# Power_P2V5.net
KiCad netlist of a schematic drawn in Altium Designer
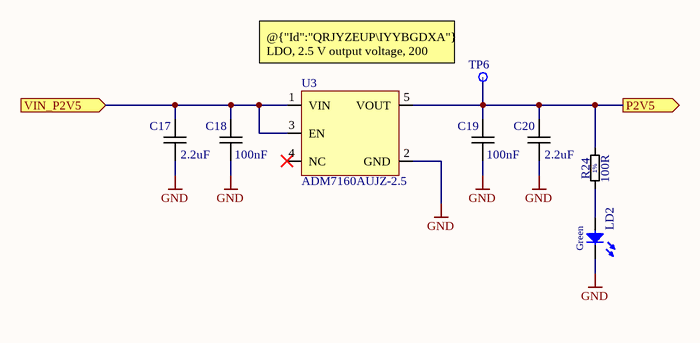
[diagram p0: Power_P2V5.SchDoc]

(export (version "E")
  (design (tool "Eeschema 10.0.6"))
  (components
    (comp (ref "C17")
      (value "2.2uF")
      (footprint "CAPC0603X90N")
      (description "Non-polarised capacitor")
      (fields (field (name "MANUFACTURER PART NUMBER") "GRM188Z71C225KE43D"))
      (libsource (lib "Capacitors") (part "Capacitor - non polarized"))
    )
    (comp (ref "C18")
      (value "100nF")
      (footprint "CAPC0603X90N")
      (description "Non-polarised capacitor")
      (fields (field (name "MANUFACTURER PART NUMBER") "VJ0603Y104KXJCW1BC"))
      (libsource (lib "Capacitors") (part "Capacitor - non polarized"))
    )
    (comp (ref "C19")
      (value "100nF")
      (footprint "CAPC0603X90N")
      (description "Non-polarised capacitor")
      (fields (field (name "MANUFACTURER PART NUMBER") "VJ0603Y104KXJCW1BC"))
      (libsource (lib "Capacitors") (part "Capacitor - non polarized"))
    )
    (comp (ref "C20")
      (value "2.2uF")
      (footprint "CAPC0603X90N")
      (description "Non-polarised capacitor")
      (fields (field (name "MANUFACTURER PART NUMBER") "GRM188Z71C225KE43D"))
      (libsource (lib "Capacitors") (part "Capacitor - non polarized"))
    )
    (comp (ref "LD2")
      (value "Green")
      (footprint "LED_0603X60N")
      (description "SMD mono-color Chip LED, Green, 0603")
      (fields (field (name "MANUFACTURER PART NUMBER") "HSME-C191"))
      (libsource (lib "ICs_and_Semiconductors") (part "LED 1C 2A"))
    )
    (comp (ref "R24")
      (value "100R")
      (footprint "RESC0603X60N")
      (description "General Purpose Thick Film Chip Resistor")
      (fields (field (name "MANUFACTURER PART NUMBER") "0603SAF1000T5E") (field (name "TOLERANCE") "1%"))
      (libsource (lib "Resistors") (part "Resistor - 1%"))
    )
    (comp (ref "TP6")
      (value "TestPoint")
      (footprint "TESTPOINT_SMD_C1P27MM")
      (description "1.27mm diameter SMD Test Point Area")
      (libsource (lib "Mechanical_and_PCB_Features") (part "Test Point"))
    )
    (comp (ref "U3")
      (value "ADM7160AUJZ-2.5")
      (footprint "SOT23-5")
      (description "Ultralow Noise, 200 mA Linear Regulator, 2.5V out")
      (libsource (lib "ICs_and_Semiconductors") (part "ADM7160AUJZ"))
    )
  )
  (nets
    (net (code "1") (name "/P2V5") (class "Default")
      (node (ref "C19") (pin "1") (pinfunction "1_1") (pintype "passive"))
      (node (ref "C20") (pin "1") (pinfunction "1_1") (pintype "passive"))
      (node (ref "R24") (pin "2") (pinfunction "2_2") (pintype "passive"))
      (node (ref "TP6") (pin "1") (pinfunction "1_1") (pintype "passive"))
      (node (ref "U3") (pin "5") (pinfunction "VOUT_5") (pintype "passive"))
    )
    (net (code "2") (name "/VIN_P2V5") (class "Default")
      (node (ref "C17") (pin "1") (pinfunction "1_1") (pintype "passive"))
      (node (ref "C18") (pin "1") (pinfunction "1_1") (pintype "passive"))
      (node (ref "U3") (pin "1") (pinfunction "VIN_1") (pintype "passive"))
      (node (ref "U3") (pin "3") (pinfunction "EN_3") (pintype "passive"))
    )
    (net (code "3") (name "GND") (class "Default")
      (node (ref "C17") (pin "2") (pinfunction "2_2") (pintype "passive"))
      (node (ref "C18") (pin "2") (pinfunction "2_2") (pintype "passive"))
      (node (ref "C19") (pin "2") (pinfunction "2_2") (pintype "passive"))
      (node (ref "C20") (pin "2") (pinfunction "2_2") (pintype "passive"))
      (node (ref "LD2") (pin "1") (pinfunction "C_1") (pintype "passive"))
      (node (ref "U3") (pin "2") (pinfunction "GND_2") (pintype "power_in"))
    )
    (net (code "4") (name "Net-(LD2-A)") (class "Default")
      (node (ref "LD2") (pin "2") (pinfunction "A_2") (pintype "passive"))
      (node (ref "R24") (pin "1") (pinfunction "1_1") (pintype "passive"))
    )
    (net (code "5") (name "unconnected-(U3-NC-Pad4)") (class "Default")
      (node (ref "U3") (pin "4") (pinfunction "NC_4") (pintype "passive+no_connect"))
    )
  )
)
